# battery_charger.net
KiCad netlist of a schematic drawn in EAGLE
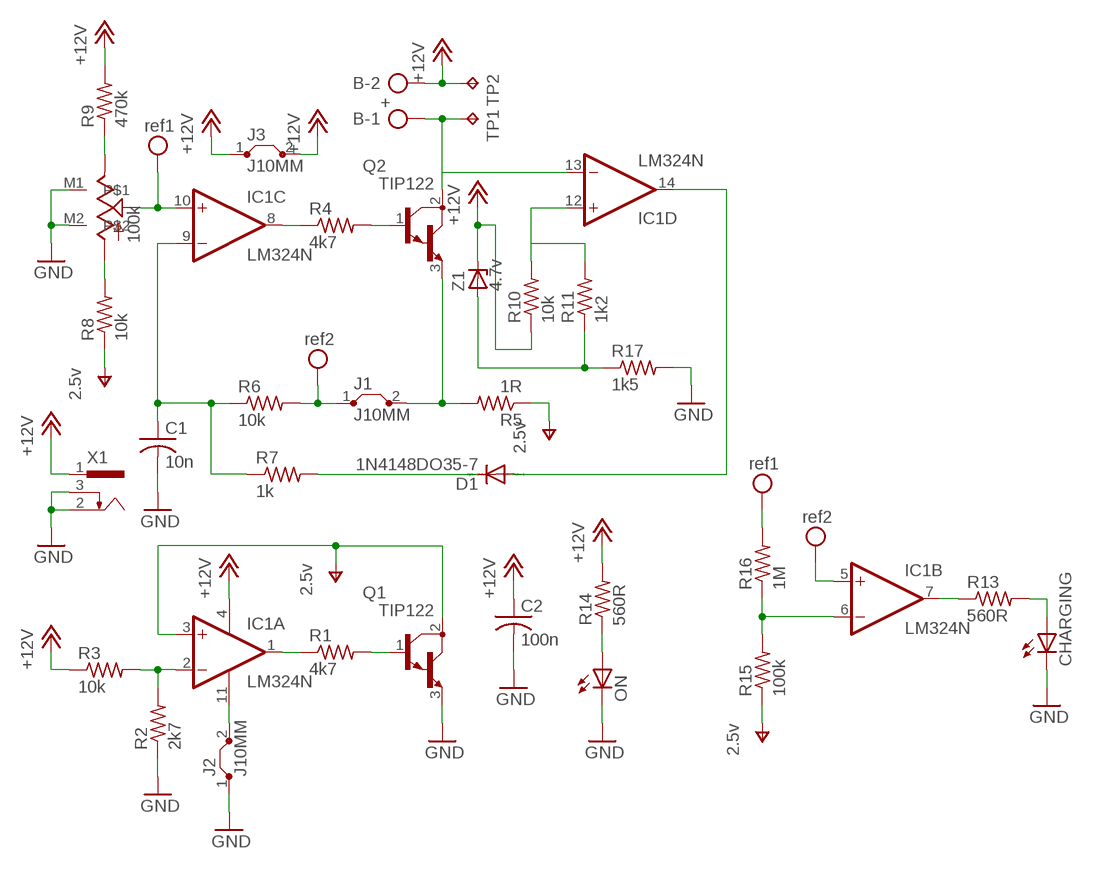
[diagram p0: schematic, sheet 1]

(export (version "E")
  (design (tool "Eeschema 10.0.6"))
  (components
    (comp (ref "B")
      (value "+")
      (footprint "eagle-import:AK500_2")
      (libsource (lib "eagle-import") (part "AK500/2"))
    )
    (comp (ref "C1")
      (value "10n")
      (footprint "eagle-import:C050-025X075")
      (libsource (lib "eagle-import") (part "C-US050-025X075"))
    )
    (comp (ref "C2")
      (value "100n")
      (footprint "eagle-import:C050-025X075")
      (libsource (lib "eagle-import") (part "C-US050-025X075"))
    )
    (comp (ref "CHARGING")
      (value "LED5MM")
      (footprint "eagle-import:LED5MM")
      (libsource (lib "eagle-import") (part "LED5MM"))
    )
    (comp (ref "D1")
      (value "1N4148DO35-7")
      (footprint "eagle-import:DO35-7")
      (libsource (lib "eagle-import") (part "1N4148DO35-7"))
    )
    (comp (ref "IC1")
      (value "LM324N")
      (footprint "eagle-import:DIL14")
      (libsource (lib "eagle-import") (part "LM324N"))
    )
    (comp (ref "J1")
      (value "J10MM")
      (footprint "eagle-import:10")
      (libsource (lib "eagle-import") (part "J10MM"))
    )
    (comp (ref "J2")
      (value "J10MM")
      (footprint "eagle-import:10")
      (libsource (lib "eagle-import") (part "J10MM"))
    )
    (comp (ref "J3")
      (value "J10MM")
      (footprint "eagle-import:10")
      (libsource (lib "eagle-import") (part "J10MM"))
    )
    (comp (ref "ON")
      (value "LED5MM")
      (footprint "eagle-import:LED5MM")
      (libsource (lib "eagle-import") (part "LED5MM"))
    )
    (comp (ref "Q1")
      (value "TIP122")
      (footprint "eagle-import:TO220V")
      (libsource (lib "eagle-import") (part "TIP122"))
    )
    (comp (ref "Q2")
      (value "TIP122")
      (footprint "eagle-import:TO220V")
      (libsource (lib "eagle-import") (part "TIP122"))
    )
    (comp (ref "R1")
      (value "4k7")
      (footprint "eagle-import:0207_7")
      (libsource (lib "eagle-import") (part "R-US_0207/7"))
    )
    (comp (ref "R2")
      (value "2k7")
      (footprint "eagle-import:0207_7")
      (libsource (lib "eagle-import") (part "R-US_0207/7"))
    )
    (comp (ref "R3")
      (value "10k")
      (footprint "eagle-import:0207_7")
      (libsource (lib "eagle-import") (part "R-US_0207/7"))
    )
    (comp (ref "R4")
      (value "4k7")
      (footprint "eagle-import:0207_7")
      (libsource (lib "eagle-import") (part "R-US_0207/7"))
    )
    (comp (ref "R5")
      (value "1R")
      (footprint "eagle-import:0922_22")
      (libsource (lib "eagle-import") (part "R-US_0922/22"))
    )
    (comp (ref "R6")
      (value "10k")
      (footprint "eagle-import:0207_7")
      (libsource (lib "eagle-import") (part "R-US_0207/7"))
    )
    (comp (ref "R7")
      (value "1k")
      (footprint "eagle-import:0207_7")
      (libsource (lib "eagle-import") (part "R-US_0207/7"))
    )
    (comp (ref "R8")
      (value "10k")
      (footprint "eagle-import:0207_7")
      (libsource (lib "eagle-import") (part "R-US_0207/7"))
    )
    (comp (ref "R9")
      (value "470k")
      (footprint "eagle-import:0207_7")
      (libsource (lib "eagle-import") (part "R-US_0207/7"))
    )
    (comp (ref "R10")
      (value "10k")
      (footprint "eagle-import:0207_7")
      (libsource (lib "eagle-import") (part "R-US_0207/7"))
    )
    (comp (ref "R11")
      (value "1k2")
      (footprint "eagle-import:0207_7")
      (libsource (lib "eagle-import") (part "R-US_0207/7"))
    )
    (comp (ref "R12")
      (value "100k")
      (footprint "eagle-import:EVUFXM")
      (libsource (lib "eagle-import") (part "US-EVUMF3"))
    )
    (comp (ref "R13")
      (value "560R")
      (footprint "eagle-import:0207_7")
      (libsource (lib "eagle-import") (part "R-US_0207/7"))
    )
    (comp (ref "R14")
      (value "560R")
      (footprint "eagle-import:0207_7")
      (libsource (lib "eagle-import") (part "R-US_0207/7"))
    )
    (comp (ref "R15")
      (value "100k")
      (footprint "eagle-import:0207_7")
      (libsource (lib "eagle-import") (part "R-US_0207/7"))
    )
    (comp (ref "R16")
      (value "1M")
      (footprint "eagle-import:0207_7")
      (libsource (lib "eagle-import") (part "R-US_0207/7"))
    )
    (comp (ref "R17")
      (value "1k5")
      (footprint "eagle-import:0207_7")
      (libsource (lib "eagle-import") (part "R-US_0207/7"))
    )
    (comp (ref "TP1")
      (value "TPPAD1-13")
      (footprint "eagle-import:P1-13")
      (libsource (lib "eagle-import") (part "TPPAD1-13"))
    )
    (comp (ref "TP2")
      (value "TPPAD1-13")
      (footprint "eagle-import:P1-13")
      (libsource (lib "eagle-import") (part "TPPAD1-13"))
    )
    (comp (ref "X1")
      (value "733980-62")
      (footprint "eagle-import:733980-62")
      (libsource (lib "eagle-import") (part "73398?0-62"))
    )
    (comp (ref "Z1")
      (value "4.7v")
      (footprint "eagle-import:DO34Z7")
      (libsource (lib "eagle-import") (part "ZENER-DIODEDO34-7"))
    )
  )
  (nets
    (net (code "1") (name "+12V") (class "Default")
      (node (ref "B") (pin "2") (pinfunction "KL_2") (pintype "passive"))
      (node (ref "C2") (pin "1") (pinfunction "1_1") (pintype "passive"))
      (node (ref "IC1") (pin "4") (pinfunction "V+_4") (pintype "power_in"))
      (node (ref "J3") (pin "1") (pinfunction "1_1") (pintype "passive"))
      (node (ref "J3") (pin "2") (pinfunction "2_2") (pintype "passive"))
      (node (ref "R10") (pin "1") (pinfunction "1_1") (pintype "passive"))
      (node (ref "R14") (pin "2") (pinfunction "2_2") (pintype "passive"))
      (node (ref "R3") (pin "1") (pinfunction "1_1") (pintype "passive"))
      (node (ref "R9") (pin "2") (pinfunction "2_2") (pintype "passive"))
      (node (ref "TP2") (pin "TP") (pinfunction "TP_TP") (pintype "input"))
      (node (ref "X1") (pin "1") (pinfunction "1_1") (pintype "passive"))
      (node (ref "Z1") (pin "C") (pinfunction "C_C") (pintype "passive"))
    )
    (net (code "2") (name "2.5v") (class "Default")
      (node (ref "IC1") (pin "3") (pinfunction "+IN_3") (pintype "input"))
      (node (ref "Q1") (pin "2") (pinfunction "C_2") (pintype "passive"))
      (node (ref "R15") (pin "1") (pinfunction "1_1") (pintype "passive"))
      (node (ref "R5") (pin "1") (pinfunction "1_1") (pintype "passive"))
      (node (ref "R8") (pin "1") (pinfunction "1_1") (pintype "passive"))
    )
    (net (code "3") (name "GND") (class "Default")
      (node (ref "C1") (pin "2") (pinfunction "2_2") (pintype "passive"))
      (node (ref "C2") (pin "2") (pinfunction "2_2") (pintype "passive"))
      (node (ref "CHARGING") (pin "K") (pinfunction "C_K") (pintype "passive"))
      (node (ref "J2") (pin "1") (pinfunction "1_1") (pintype "passive"))
      (node (ref "ON") (pin "K") (pinfunction "C_K") (pintype "passive"))
      (node (ref "Q1") (pin "3") (pinfunction "E_3") (pintype "passive"))
      (node (ref "R12") (pin "M1") (pinfunction "P$1_M1") (pintype "bidirectional"))
      (node (ref "R12") (pin "M2") (pinfunction "P$2_M2") (pintype "bidirectional"))
      (node (ref "R17") (pin "2") (pinfunction "2_2") (pintype "passive"))
      (node (ref "R2") (pin "1") (pinfunction "1_1") (pintype "passive"))
      (node (ref "X1") (pin "2") (pinfunction "2_2") (pintype "passive"))
      (node (ref "X1") (pin "3") (pinfunction "3_3") (pintype "passive"))
    )
    (net (code "4") (name "Net-(BA-KL)") (class "Default")
      (node (ref "B") (pin "1") (pinfunction "KL_1") (pintype "passive"))
      (node (ref "IC1") (pin "13") (pinfunction "-IN_13") (pintype "input"))
      (node (ref "Q2") (pin "2") (pinfunction "C_2") (pintype "passive"))
      (node (ref "TP1") (pin "TP") (pinfunction "TP_TP") (pintype "input"))
    )
    (net (code "5") (name "Net-(CHARGING-PadA)") (class "Default")
      (node (ref "CHARGING") (pin "A") (pinfunction "A_A") (pintype "passive"))
      (node (ref "R13") (pin "2") (pinfunction "2_2") (pintype "passive"))
    )
    (net (code "6") (name "Net-(D1-PadC)") (class "Default")
      (node (ref "D1") (pin "C") (pinfunction "C_C") (pintype "passive"))
      (node (ref "R7") (pin "2") (pinfunction "2_2") (pintype "passive"))
    )
    (net (code "7") (name "Net-(IC1A--IN)") (class "Default")
      (node (ref "IC1") (pin "2") (pinfunction "-IN_2") (pintype "input"))
      (node (ref "R2") (pin "2") (pinfunction "2_2") (pintype "passive"))
      (node (ref "R3") (pin "2") (pinfunction "2_2") (pintype "passive"))
    )
    (net (code "8") (name "Net-(IC1A-OUT)") (class "Default")
      (node (ref "IC1") (pin "1") (pinfunction "OUT_1") (pintype "output"))
      (node (ref "R1") (pin "1") (pinfunction "1_1") (pintype "passive"))
    )
    (net (code "9") (name "Net-(IC1B--IN)") (class "Default")
      (node (ref "IC1") (pin "6") (pinfunction "-IN_6") (pintype "input"))
      (node (ref "R15") (pin "2") (pinfunction "2_2") (pintype "passive"))
      (node (ref "R16") (pin "1") (pinfunction "1_1") (pintype "passive"))
    )
    (net (code "10") (name "Net-(IC1B-OUT)") (class "Default")
      (node (ref "IC1") (pin "7") (pinfunction "OUT_7") (pintype "output"))
      (node (ref "R13") (pin "1") (pinfunction "1_1") (pintype "passive"))
    )
    (net (code "11") (name "Net-(IC1C--IN)") (class "Default")
      (node (ref "C1") (pin "1") (pinfunction "1_1") (pintype "passive"))
      (node (ref "IC1") (pin "9") (pinfunction "-IN_9") (pintype "input"))
      (node (ref "R6") (pin "1") (pinfunction "1_1") (pintype "passive"))
      (node (ref "R7") (pin "1") (pinfunction "1_1") (pintype "passive"))
    )
    (net (code "12") (name "Net-(IC1C-OUT)") (class "Default")
      (node (ref "IC1") (pin "8") (pinfunction "OUT_8") (pintype "output"))
      (node (ref "R4") (pin "1") (pinfunction "1_1") (pintype "passive"))
    )
    (net (code "13") (name "Net-(IC1D-+IN)") (class "Default")
      (node (ref "IC1") (pin "12") (pinfunction "+IN_12") (pintype "input"))
      (node (ref "R10") (pin "2") (pinfunction "2_2") (pintype "passive"))
      (node (ref "R11") (pin "2") (pinfunction "2_2") (pintype "passive"))
    )
    (net (code "14") (name "Net-(IC1D-OUT)") (class "Default")
      (node (ref "D1") (pin "A") (pinfunction "A_A") (pintype "passive"))
      (node (ref "IC1") (pin "14") (pinfunction "OUT_14") (pintype "output"))
    )
    (net (code "15") (name "Net-(IC1E-V-)") (class "Default")
      (node (ref "IC1") (pin "11") (pinfunction "V-_11") (pintype "power_in"))
      (node (ref "J2") (pin "2") (pinfunction "2_2") (pintype "passive"))
    )
    (net (code "16") (name "Net-(ON-PadA)") (class "Default")
      (node (ref "ON") (pin "A") (pinfunction "A_A") (pintype "passive"))
      (node (ref "R14") (pin "1") (pinfunction "1_1") (pintype "passive"))
    )
    (net (code "17") (name "Net-(Q1-B)") (class "Default")
      (node (ref "Q1") (pin "1") (pinfunction "B_1") (pintype "passive"))
      (node (ref "R1") (pin "2") (pinfunction "2_2") (pintype "passive"))
    )
    (net (code "18") (name "Net-(Q2-B)") (class "Default")
      (node (ref "Q2") (pin "1") (pinfunction "B_1") (pintype "passive"))
      (node (ref "R4") (pin "2") (pinfunction "2_2") (pintype "passive"))
    )
    (net (code "19") (name "Net-(Q2-E)") (class "Default")
      (node (ref "J1") (pin "2") (pinfunction "2_2") (pintype "passive"))
      (node (ref "Q2") (pin "3") (pinfunction "E_3") (pintype "passive"))
      (node (ref "R5") (pin "2") (pinfunction "2_2") (pintype "passive"))
    )
    (net (code "20") (name "Net-(R11-Pad1)") (class "Default")
      (node (ref "R11") (pin "1") (pinfunction "1_1") (pintype "passive"))
      (node (ref "R17") (pin "1") (pinfunction "1_1") (pintype "passive"))
      (node (ref "Z1") (pin "A") (pinfunction "A_A") (pintype "passive"))
    )
    (net (code "21") (name "Net-(R12-A)") (class "Default")
      (node (ref "R12") (pin "1") (pinfunction "A_1") (pintype "passive"))
      (node (ref "R8") (pin "2") (pinfunction "2_2") (pintype "passive"))
    )
    (net (code "22") (name "Net-(R12-E)") (class "Default")
      (node (ref "R12") (pin "3") (pinfunction "E_3") (pintype "passive"))
      (node (ref "R9") (pin "1") (pinfunction "1_1") (pintype "passive"))
    )
    (net (code "23") (name "ref1") (class "Default")
      (node (ref "IC1") (pin "10") (pinfunction "+IN_10") (pintype "input"))
      (node (ref "R12") (pin "2") (pinfunction "S_2") (pintype "passive"))
      (node (ref "R16") (pin "2") (pinfunction "2_2") (pintype "passive"))
    )
    (net (code "24") (name "ref2") (class "Default")
      (node (ref "IC1") (pin "5") (pinfunction "+IN_5") (pintype "input"))
      (node (ref "J1") (pin "1") (pinfunction "1_1") (pintype "passive"))
      (node (ref "R6") (pin "2") (pinfunction "2_2") (pintype "passive"))
    )
  )
)
